# Sheet1.net
KiCad netlist of a schematic drawn in Altium Designer
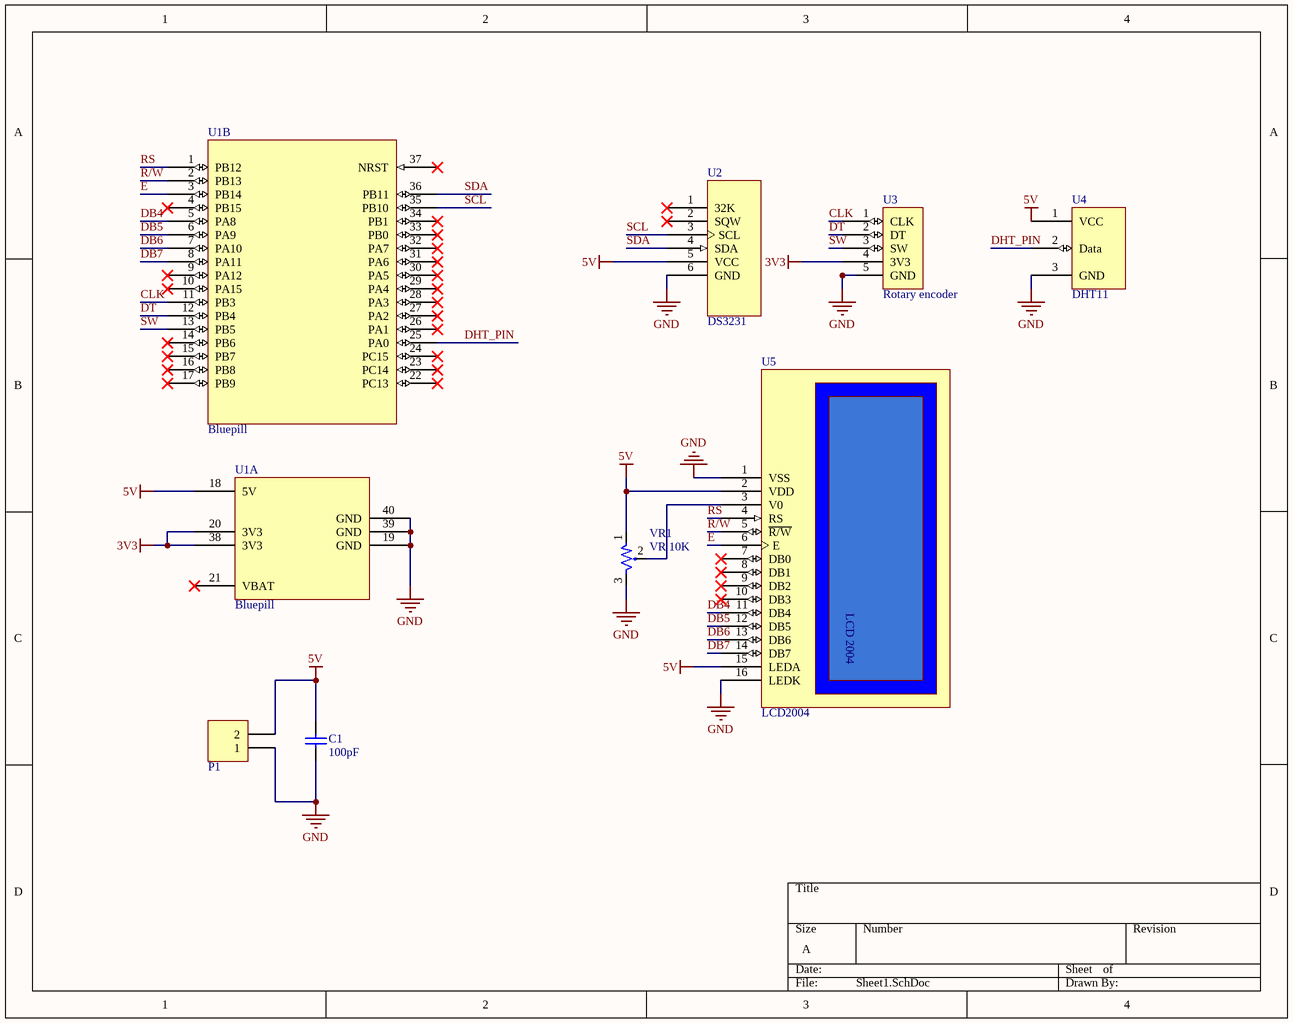
[diagram p0: Sheet1.SchDoc]

(export (version "E")
  (design (tool "Eeschema 10.0.6"))
  (components
    (comp (ref "C1")
      (value "100pF")
      (footprint "CN1")
      (description "Capacitor")
      (fields (field (name "Comment") "Cap Non-Pol"))
      (libsource (lib "PIF_Library") (part "Cap Non-Pol"))
    )
    (comp (ref "P1")
      (value "Domino 2")
      (footprint "DOMINO 2- 5mm")
      (description "Domino, 2-Pin")
      (fields (field (name "PUBLISHER") "Altium Limited"))
      (libsource (lib "PIF_Library") (part "Domino 2"))
    )
    (comp (ref "U1")
      (value "Bluepill")
      (footprint "Bluepill")
      (fields (field (name "MANUFACTURER") "STMicroelectronics"))
      (libsource (lib "BTVN") (part "STM32F103C8T6"))
    )
    (comp (ref "U2") (value "DS3231") (footprint "DS3231") (libsource (lib "BT2") (part "DS3231")))
    (comp (ref "U3")
      (value "Rotary encoder")
      (footprint "Rotary Encoder")
      (libsource (lib "BT2") (part "Rotary encoder"))
    )
    (comp (ref "U4") (value "DHT11") (footprint "DH11") (libsource (lib "BT2") (part "DHT11")))
    (comp (ref "U5")
      (value "LCD2004")
      (footprint "LCD2004")
      (fields (field (name "MANUFACTURER") "AZ Display"))
      (libsource (lib "BTVN") (part "LCD2004"))
    )
    (comp (ref "VR1")
      (value "VR 10K")
      (footprint "Varistor 1")
      (description "Var Resistor")
      (fields (field (name "Comment") "10K"))
      (libsource (lib "PIF_Library") (part "Var Resistor"))
    )
  )
  (nets
    (net (code "1") (name "/CLK") (class "Default")
      (node (ref "U1") (pin "11") (pinfunction "PB3_11") (pintype "bidirectional"))
      (node (ref "U3") (pin "1") (pinfunction "CLK_1") (pintype "bidirectional"))
    )
    (net (code "2") (name "/DB4") (class "Default")
      (node (ref "U1") (pin "5") (pinfunction "PA8_5") (pintype "bidirectional"))
      (node (ref "U5") (pin "11") (pinfunction "DB4_11") (pintype "bidirectional"))
    )
    (net (code "3") (name "/DB5") (class "Default")
      (node (ref "U1") (pin "6") (pinfunction "PA9_6") (pintype "bidirectional"))
      (node (ref "U5") (pin "12") (pinfunction "DB5_12") (pintype "bidirectional"))
    )
    (net (code "4") (name "/DB6") (class "Default")
      (node (ref "U1") (pin "7") (pinfunction "PA10_7") (pintype "bidirectional"))
      (node (ref "U5") (pin "13") (pinfunction "DB6_13") (pintype "bidirectional"))
    )
    (net (code "5") (name "/DB7") (class "Default")
      (node (ref "U1") (pin "8") (pinfunction "PA11_8") (pintype "bidirectional"))
      (node (ref "U5") (pin "14") (pinfunction "DB7_14") (pintype "bidirectional"))
    )
    (net (code "6") (name "/DHT_PIN") (class "Default")
      (node (ref "U1") (pin "25") (pinfunction "PA0_25") (pintype "bidirectional"))
      (node (ref "U4") (pin "2") (pinfunction "Data_2") (pintype "bidirectional"))
    )
    (net (code "7") (name "/DT") (class "Default")
      (node (ref "U1") (pin "12") (pinfunction "PB4_12") (pintype "bidirectional"))
      (node (ref "U3") (pin "2") (pinfunction "DT_2") (pintype "bidirectional"))
    )
    (net (code "8") (name "/E") (class "Default")
      (node (ref "U1") (pin "3") (pinfunction "PB14_3") (pintype "bidirectional"))
      (node (ref "U5") (pin "6") (pinfunction "E_6") (pintype "passive"))
    )
    (net (code "9") (name "/RS") (class "Default")
      (node (ref "U1") (pin "1") (pinfunction "PB12_1") (pintype "bidirectional"))
      (node (ref "U5") (pin "4") (pinfunction "RS_4") (pintype "input"))
    )
    (net (code "10") (name "/R{slash}W") (class "Default")
      (node (ref "U1") (pin "2") (pinfunction "PB13_2") (pintype "bidirectional"))
      (node (ref "U5") (pin "5") (pinfunction "~{R/W}_5") (pintype "bidirectional"))
    )
    (net (code "11") (name "/SCL") (class "Default")
      (node (ref "U1") (pin "35") (pinfunction "PB10_35") (pintype "bidirectional"))
      (node (ref "U2") (pin "3") (pinfunction "SCL_3") (pintype "passive"))
    )
    (net (code "12") (name "/SDA") (class "Default")
      (node (ref "U1") (pin "36") (pinfunction "PB11_36") (pintype "bidirectional"))
      (node (ref "U2") (pin "4") (pinfunction "SDA_4") (pintype "input"))
    )
    (net (code "13") (name "/SW") (class "Default")
      (node (ref "U1") (pin "13") (pinfunction "PB5_13") (pintype "bidirectional"))
      (node (ref "U3") (pin "3") (pinfunction "SW_3") (pintype "bidirectional"))
    )
    (net (code "14") (name "3V3") (class "Default")
      (node (ref "U1") (pin "20") (pinfunction "3V3_20") (pintype "passive"))
      (node (ref "U1") (pin "38") (pinfunction "3V3_38") (pintype "passive"))
      (node (ref "U3") (pin "4") (pinfunction "3V3_4") (pintype "passive"))
    )
    (net (code "15") (name "5V") (class "Default")
      (node (ref "C1") (pin "2") (pinfunction "2_2") (pintype "passive"))
      (node (ref "P1") (pin "2") (pinfunction "2_2") (pintype "passive"))
      (node (ref "U1") (pin "18") (pinfunction "5V_18") (pintype "passive"))
      (node (ref "U2") (pin "5") (pinfunction "VCC_5") (pintype "passive"))
      (node (ref "U4") (pin "1") (pinfunction "VCC_1") (pintype "passive"))
      (node (ref "U5") (pin "15") (pinfunction "LEDA_15") (pintype "passive"))
      (node (ref "U5") (pin "2") (pinfunction "VDD_2") (pintype "passive"))
      (node (ref "VR1") (pin "1") (pinfunction "1_1") (pintype "passive"))
    )
    (net (code "16") (name "GND") (class "Default")
      (node (ref "C1") (pin "1") (pinfunction "1_1") (pintype "passive"))
      (node (ref "P1") (pin "1") (pinfunction "1_1") (pintype "passive"))
      (node (ref "U1") (pin "19") (pinfunction "GND_19") (pintype "passive"))
      (node (ref "U1") (pin "39") (pinfunction "GND_39") (pintype "passive"))
      (node (ref "U1") (pin "40") (pinfunction "GND_40") (pintype "passive"))
      (node (ref "U2") (pin "6") (pinfunction "GND_6") (pintype "passive"))
      (node (ref "U3") (pin "5") (pinfunction "GND_5") (pintype "passive"))
      (node (ref "U4") (pin "3") (pinfunction "GND_3") (pintype "passive"))
      (node (ref "U5") (pin "1") (pinfunction "VSS_1") (pintype "passive"))
      (node (ref "U5") (pin "16") (pinfunction "LEDK_16") (pintype "passive"))
      (node (ref "VR1") (pin "3") (pinfunction "3_3") (pintype "passive"))
    )
    (net (code "17") (name "Net-(U5-V0)") (class "Default")
      (node (ref "U5") (pin "3") (pinfunction "V0_3") (pintype "passive"))
      (node (ref "VR1") (pin "2") (pinfunction "2_2") (pintype "passive"))
    )
    (net (code "18") (name "unconnected-(U1A-VBAT-Pad21)") (class "Default")
      (node (ref "U1") (pin "21") (pinfunction "VBAT_21") (pintype "passive+no_connect"))
    )
    (net (code "19") (name "unconnected-(U1B-NRST-Pad37)") (class "Default")
      (node (ref "U1") (pin "37") (pinfunction "NRST_37") (pintype "input+no_connect"))
    )
    (net (code "20") (name "unconnected-(U1B-PA1-Pad26)") (class "Default")
      (node (ref "U1") (pin "26") (pinfunction "PA1_26") (pintype "bidirectional+no_connect"))
    )
    (net (code "21") (name "unconnected-(U1B-PA2-Pad27)") (class "Default")
      (node (ref "U1") (pin "27") (pinfunction "PA2_27") (pintype "bidirectional+no_connect"))
    )
    (net (code "22") (name "unconnected-(U1B-PA3-Pad28)") (class "Default")
      (node (ref "U1") (pin "28") (pinfunction "PA3_28") (pintype "bidirectional+no_connect"))
    )
    (net (code "23") (name "unconnected-(U1B-PA4-Pad29)") (class "Default")
      (node (ref "U1") (pin "29") (pinfunction "PA4_29") (pintype "bidirectional+no_connect"))
    )
    (net (code "24") (name "unconnected-(U1B-PA5-Pad30)") (class "Default")
      (node (ref "U1") (pin "30") (pinfunction "PA5_30") (pintype "bidirectional+no_connect"))
    )
    (net (code "25") (name "unconnected-(U1B-PA6-Pad31)") (class "Default")
      (node (ref "U1") (pin "31") (pinfunction "PA6_31") (pintype "bidirectional+no_connect"))
    )
    (net (code "26") (name "unconnected-(U1B-PA7-Pad32)") (class "Default")
      (node (ref "U1") (pin "32") (pinfunction "PA7_32") (pintype "bidirectional+no_connect"))
    )
    (net (code "27") (name "unconnected-(U1B-PA12-Pad9)") (class "Default")
      (node (ref "U1") (pin "9") (pinfunction "PA12_9") (pintype "bidirectional+no_connect"))
    )
    (net (code "28") (name "unconnected-(U1B-PA15-Pad10)") (class "Default")
      (node (ref "U1") (pin "10") (pinfunction "PA15_10") (pintype "bidirectional+no_connect"))
    )
    (net (code "29") (name "unconnected-(U1B-PB0-Pad33)") (class "Default")
      (node (ref "U1") (pin "33") (pinfunction "PB0_33") (pintype "bidirectional+no_connect"))
    )
    (net (code "30") (name "unconnected-(U1B-PB1-Pad34)") (class "Default")
      (node (ref "U1") (pin "34") (pinfunction "PB1_34") (pintype "bidirectional+no_connect"))
    )
    (net (code "31") (name "unconnected-(U1B-PB6-Pad14)") (class "Default")
      (node (ref "U1") (pin "14") (pinfunction "PB6_14") (pintype "bidirectional+no_connect"))
    )
    (net (code "32") (name "unconnected-(U1B-PB7-Pad15)") (class "Default")
      (node (ref "U1") (pin "15") (pinfunction "PB7_15") (pintype "bidirectional+no_connect"))
    )
    (net (code "33") (name "unconnected-(U1B-PB8-Pad16)") (class "Default")
      (node (ref "U1") (pin "16") (pinfunction "PB8_16") (pintype "bidirectional+no_connect"))
    )
    (net (code "34") (name "unconnected-(U1B-PB9-Pad17)") (class "Default")
      (node (ref "U1") (pin "17") (pinfunction "PB9_17") (pintype "bidirectional+no_connect"))
    )
    (net (code "35") (name "unconnected-(U1B-PB15-Pad4)") (class "Default")
      (node (ref "U1") (pin "4") (pinfunction "PB15_4") (pintype "bidirectional+no_connect"))
    )
    (net (code "36") (name "unconnected-(U1B-PC13-Pad22)") (class "Default")
      (node (ref "U1") (pin "22") (pinfunction "PC13_22") (pintype "bidirectional+no_connect"))
    )
    (net (code "37") (name "unconnected-(U1B-PC14-Pad23)") (class "Default")
      (node (ref "U1") (pin "23") (pinfunction "PC14_23") (pintype "bidirectional+no_connect"))
    )
    (net (code "38") (name "unconnected-(U1B-PC15-Pad24)") (class "Default")
      (node (ref "U1") (pin "24") (pinfunction "PC15_24") (pintype "bidirectional+no_connect"))
    )
    (net (code "39") (name "unconnected-(U2-32K-Pad1)") (class "Default")
      (node (ref "U2") (pin "1") (pinfunction "32K_1") (pintype "passive+no_connect"))
    )
    (net (code "40") (name "unconnected-(U2-SQW-Pad2)") (class "Default")
      (node (ref "U2") (pin "2") (pinfunction "SQW_2") (pintype "passive+no_connect"))
    )
    (net (code "41") (name "unconnected-(U5-DB0-Pad7)") (class "Default")
      (node (ref "U5") (pin "7") (pinfunction "DB0_7") (pintype "bidirectional+no_connect"))
    )
    (net (code "42") (name "unconnected-(U5-DB1-Pad8)") (class "Default")
      (node (ref "U5") (pin "8") (pinfunction "DB1_8") (pintype "bidirectional+no_connect"))
    )
    (net (code "43") (name "unconnected-(U5-DB2-Pad9)") (class "Default")
      (node (ref "U5") (pin "9") (pinfunction "DB2_9") (pintype "bidirectional+no_connect"))
    )
    (net (code "44") (name "unconnected-(U5-DB3-Pad10)") (class "Default")
      (node (ref "U5") (pin "10") (pinfunction "DB3_10") (pintype "bidirectional+no_connect"))
    )
  )
)
